# 4_Temperature_Sensor.net
KiCad netlist of a schematic drawn in Altium Designer
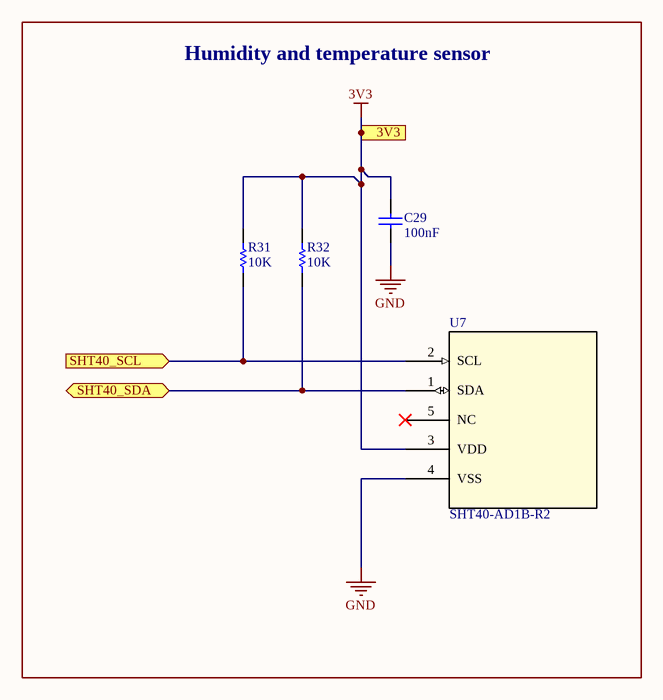
[diagram p0: [4] Temperature_Sensor.SchDoc]

(export (version "E")
  (design (tool "Eeschema 10.0.6"))
  (components
    (comp (ref "C29")
      (value "100nF")
      (footprint "Capacitor 0402")
      (description "Capacitor Ceramico SMD 0402")
      (libsource (lib "Mi Libreria") (part "Capacitor 0402"))
    )
    (comp (ref "R31")
      (value "10K")
      (footprint "Resistencia 0402")
      (description "Resistencia SMD 0402")
      (libsource (lib "Mi Libreria") (part "Resistencia SMD 0402"))
    )
    (comp (ref "R32")
      (value "10K")
      (footprint "Resistencia 0402")
      (description "Resistencia SMD 0402")
      (libsource (lib "Mi Libreria") (part "Resistencia SMD 0402"))
    )
    (comp (ref "U7")
      (value "SHT40-AD1B-R2")
      (footprint "SHT4x_SEN")
      (description "Humidity, Temperature 0 ~ 100% RH I2C ±1.8% RH Surface Mount")
      (fields (field (name "COPYRIGHT") "Copyright (C) 2026 Ultra Librarian. All rights reserved."))
      (libsource (lib "SHT40-AD1B-R2") (part "SHT40-AD1B-R2"))
    )
  )
  (nets
    (net (code "1") (name "/SHT40_SCL") (class "Default")
      (node (ref "R31") (pin "1") (pinfunction "A_1") (pintype "passive"))
      (node (ref "U7") (pin "2") (pinfunction "SCL_2") (pintype "input"))
    )
    (net (code "2") (name "/SHT40_SDA") (class "Default")
      (node (ref "R32") (pin "1") (pinfunction "A_1") (pintype "passive"))
      (node (ref "U7") (pin "1") (pinfunction "SDA_1") (pintype "bidirectional"))
    )
    (net (code "3") (name "3V3") (class "Default")
      (node (ref "C29") (pin "2") (pinfunction "2_2") (pintype "passive"))
      (node (ref "R31") (pin "2") (pinfunction "B_2") (pintype "passive"))
      (node (ref "R32") (pin "2") (pinfunction "B_2") (pintype "passive"))
      (node (ref "U7") (pin "3") (pinfunction "VDD_3") (pintype "power_in"))
    )
    (net (code "4") (name "GND") (class "Default")
      (node (ref "C29") (pin "1") (pinfunction "1_1") (pintype "passive"))
      (node (ref "U7") (pin "4") (pinfunction "VSS_4") (pintype "power_in"))
    )
    (net (code "5") (name "unconnected-(U7-NC-Pad5)") (class "Default")
      (node (ref "U7") (pin "5") (pinfunction "NC_5") (pintype "passive+no_connect"))
    )
  )
)
